# WaterFlowSensor-RJ11-Adaptor-V2_0.net
KiCad netlist of a schematic drawn in EAGLE
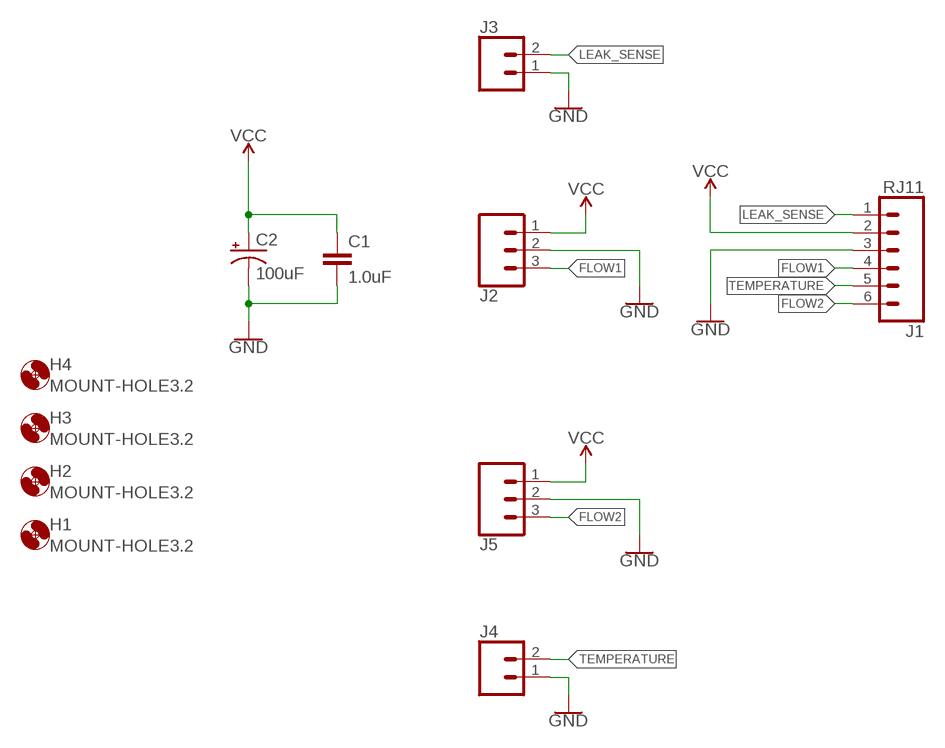
[diagram p0: schematic, sheet 1]

(export (version "E")
  (design (tool "Eeschema 10.0.6"))
  (components
    (comp (ref "C1")
      (value "1.0uF")
      (footprint "eagle-import:0805")
      (libsource (lib "eagle-import") (part "1.0UF-0805-25V-(+80/-20%)"))
    )
    (comp (ref "C2")
      (value "100uF")
      (footprint "eagle-import:CPOL-RADIAL-2.5MM-6.5MM")
      (libsource (lib "eagle-import") (part "100UF-POLAR-RADIAL-2.5MM-25V-20%"))
    )
    (comp (ref "H1")
      (value "MOUNT-HOLE3.2")
      (footprint "eagle-import:3,2")
      (libsource (lib "eagle-import") (part "MOUNT-HOLE3.2"))
    )
    (comp (ref "H2")
      (value "MOUNT-HOLE3.2")
      (footprint "eagle-import:3,2")
      (libsource (lib "eagle-import") (part "MOUNT-HOLE3.2"))
    )
    (comp (ref "H3")
      (value "MOUNT-HOLE3.2")
      (footprint "eagle-import:3,2")
      (libsource (lib "eagle-import") (part "MOUNT-HOLE3.2"))
    )
    (comp (ref "H4")
      (value "MOUNT-HOLE3.2")
      (footprint "eagle-import:3,2")
      (libsource (lib "eagle-import") (part "MOUNT-HOLE3.2"))
    )
    (comp (ref "J1")
      (value "RJ11")
      (footprint "eagle-import:RJ11-6")
      (libsource (lib "eagle-import") (part "RJ11-6"))
    )
    (comp (ref "J2")
      (value "CONN_03JST-HX-PTH-VERT")
      (footprint "eagle-import:JST-HX-3-PTH-VERT")
      (libsource (lib "eagle-import") (part "CONN_03JST-HX-PTH-VERT"))
    )
    (comp (ref "J3")
      (value "CONN_02")
      (footprint "eagle-import:1X02")
      (libsource (lib "eagle-import") (part "CONN_02"))
    )
    (comp (ref "J4")
      (value "CONN_02POLAR")
      (footprint "eagle-import:MOLEX-1X2")
      (libsource (lib "eagle-import") (part "CONN_02POLAR"))
    )
    (comp (ref "J5")
      (value "CONN_03JST-HX-PTH-VERT")
      (footprint "eagle-import:JST-HX-3-PTH-VERT")
      (libsource (lib "eagle-import") (part "CONN_03JST-HX-PTH-VERT"))
    )
  )
  (nets
    (net (code "1") (name "FLOW1") (class "Default")
      (node (ref "J1") (pin "4") (pinfunction "4_4") (pintype "passive"))
      (node (ref "J2") (pin "3") (pinfunction "3_3") (pintype "passive"))
    )
    (net (code "2") (name "FLOW2") (class "Default")
      (node (ref "J1") (pin "6") (pinfunction "6_6") (pintype "passive"))
      (node (ref "J5") (pin "3") (pinfunction "3_3") (pintype "passive"))
    )
    (net (code "3") (name "GND") (class "Default")
      (node (ref "C1") (pin "2") (pinfunction "2_2") (pintype "passive"))
      (node (ref "C2") (pin "2") (pinfunction "-_2") (pintype "passive"))
      (node (ref "J1") (pin "3") (pinfunction "3_3") (pintype "passive"))
      (node (ref "J2") (pin "2") (pinfunction "2_2") (pintype "passive"))
      (node (ref "J3") (pin "1") (pinfunction "1_1") (pintype "passive"))
      (node (ref "J4") (pin "1") (pinfunction "1_1") (pintype "passive"))
      (node (ref "J5") (pin "2") (pinfunction "2_2") (pintype "passive"))
    )
    (net (code "4") (name "LEAK_SENSE") (class "Default")
      (node (ref "J1") (pin "1") (pinfunction "1_1") (pintype "passive"))
      (node (ref "J3") (pin "2") (pinfunction "2_2") (pintype "passive"))
    )
    (net (code "5") (name "TEMPERATURE") (class "Default")
      (node (ref "J1") (pin "5") (pinfunction "5_5") (pintype "passive"))
      (node (ref "J4") (pin "2") (pinfunction "2_2") (pintype "passive"))
    )
    (net (code "6") (name "VCC") (class "Default")
      (node (ref "C1") (pin "1") (pinfunction "1_1") (pintype "passive"))
      (node (ref "C2") (pin "1") (pinfunction "+_1") (pintype "passive"))
      (node (ref "J1") (pin "2") (pinfunction "2_2") (pintype "passive"))
      (node (ref "J2") (pin "1") (pinfunction "1_1") (pintype "passive"))
      (node (ref "J5") (pin "1") (pinfunction "1_1") (pintype "passive"))
    )
  )
)
